# pc_healthypi_move_nRF5340_v5.net
KiCad netlist of a schematic drawn in EAGLE
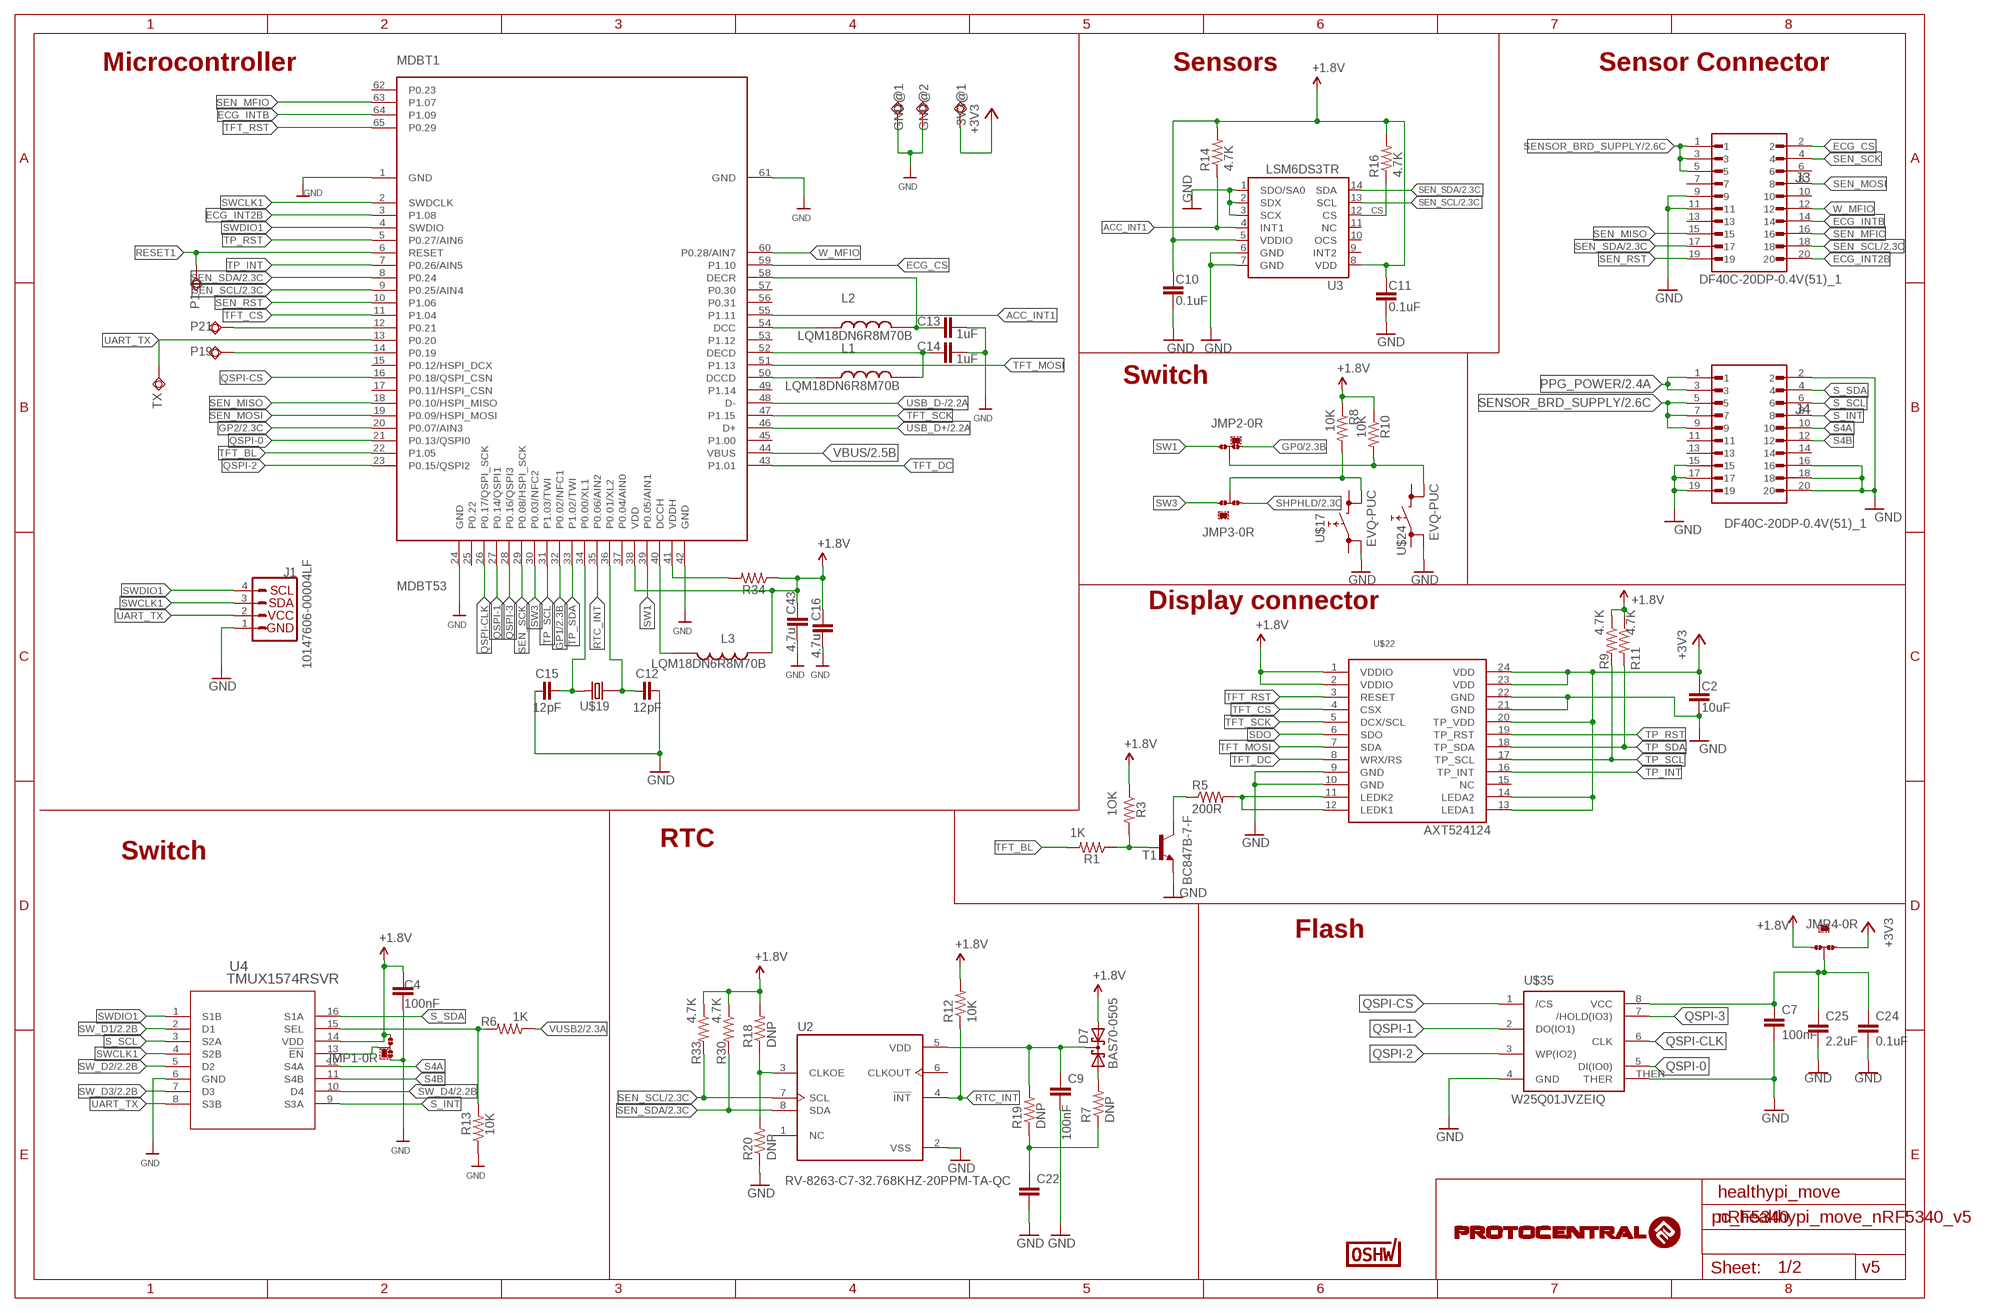
[diagram p0: schematic, sheet 1]
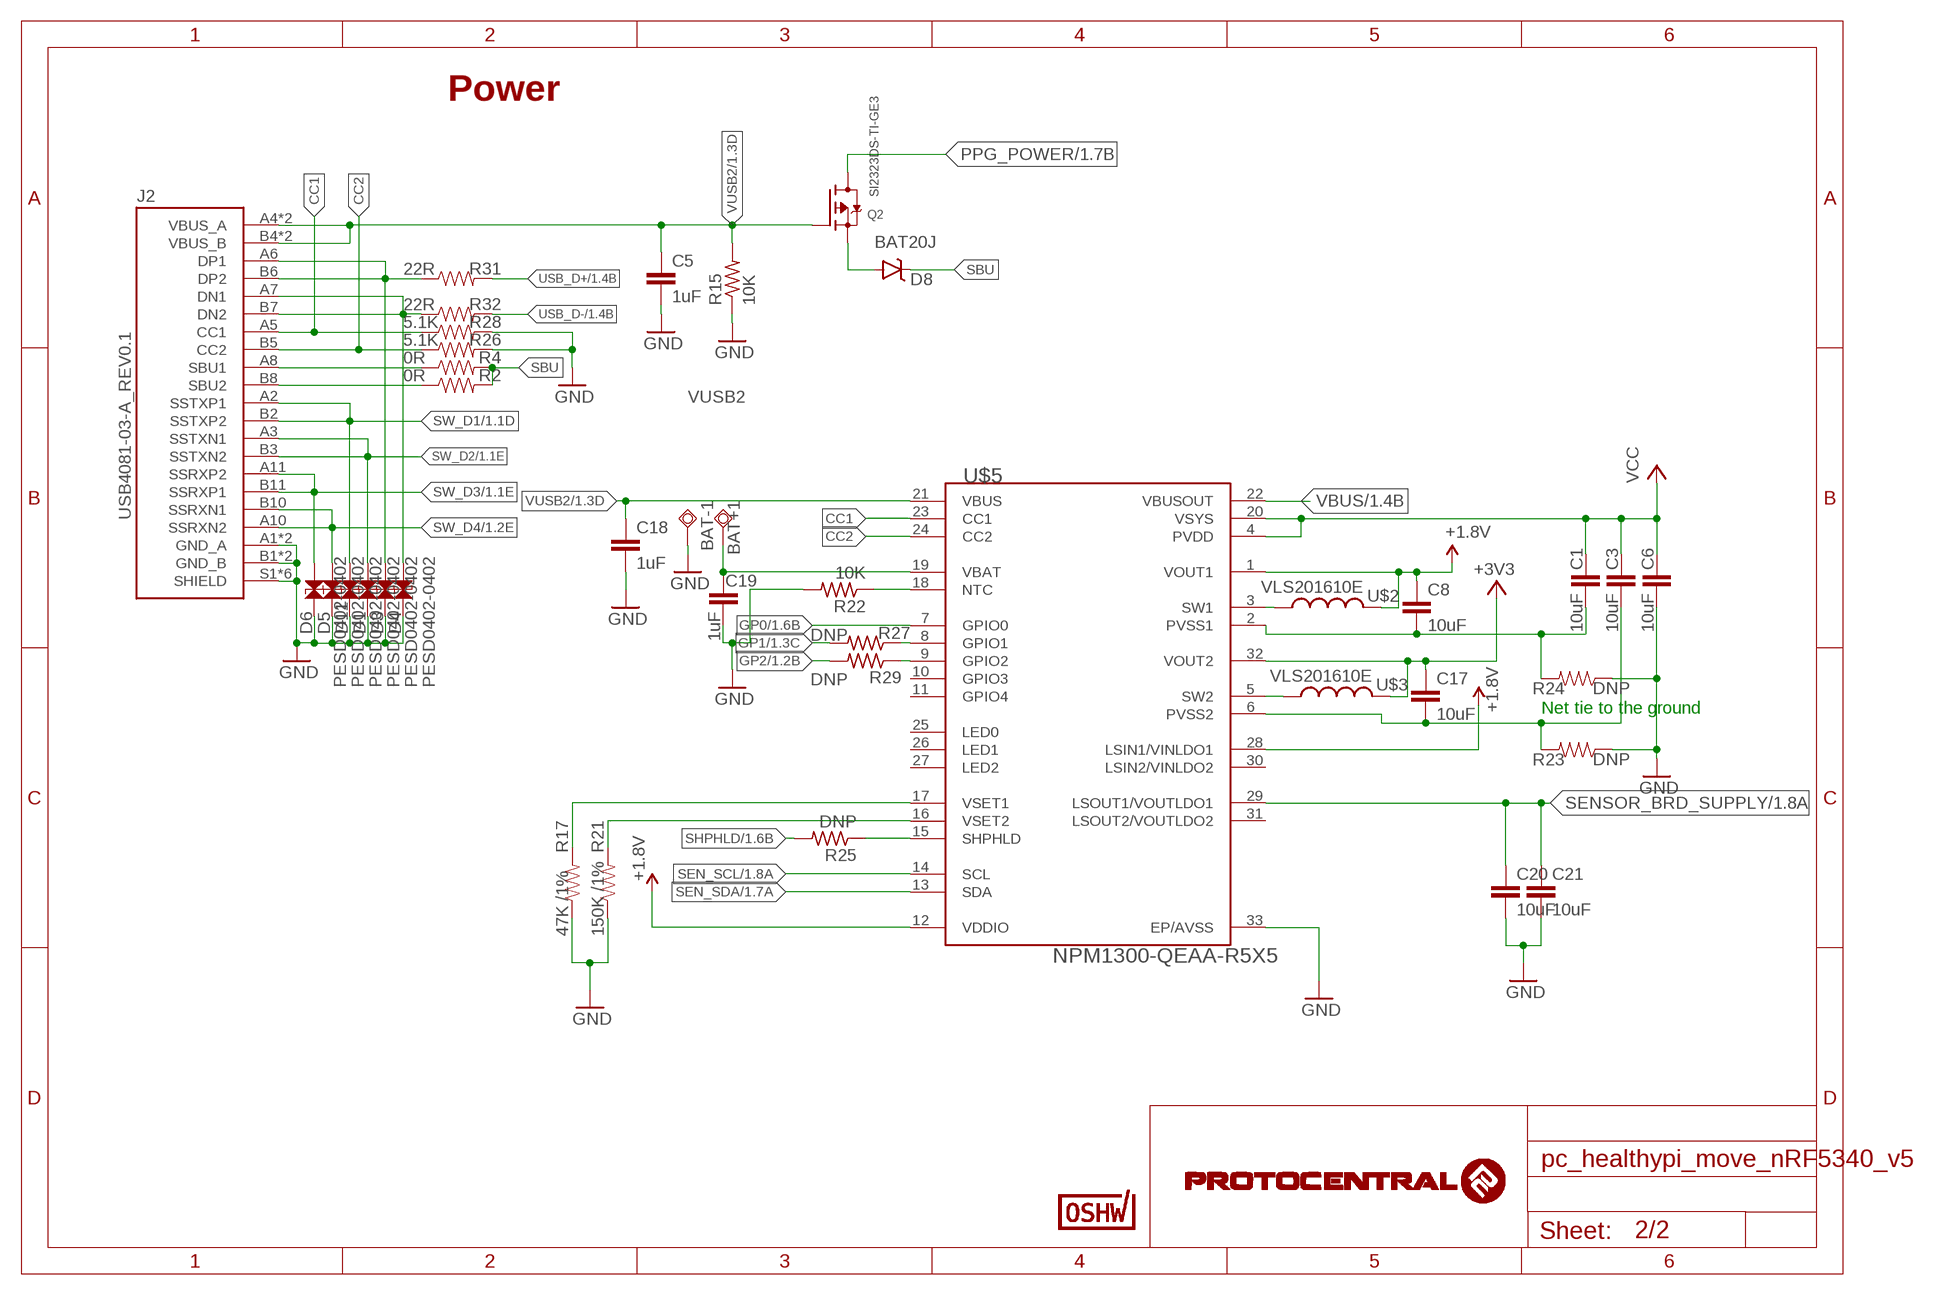
[diagram p1: schematic, sheet 2]

(export (version "E")
  (design (tool "Eeschema 10.0.6"))
  (components
    (comp (ref "BAT+1")
      (value "TPSQTP13SQ")
      (footprint "eagle-import:TP13SQ")
      (libsource (lib "eagle-import") (part "TPSQTP13SQ"))
    )
    (comp (ref "BAT-1")
      (value "TPSQTP13SQ")
      (footprint "eagle-import:TP13SQ")
      (libsource (lib "eagle-import") (part "TPSQTP13SQ"))
    )
    (comp (ref "C1")
      (value "10uF")
      (footprint "eagle-import:0402-TIGHT")
      (libsource (lib "eagle-import") (part "2.2UF-0402_TIGHT-10V-10%-X5R"))
    )
    (comp (ref "C3")
      (value "10uF")
      (footprint "eagle-import:0402-TIGHT")
      (libsource (lib "eagle-import") (part "2.2UF-0402_TIGHT-10V-10%-X5R"))
    )
    (comp (ref "C5")
      (value "1uF")
      (footprint "eagle-import:0402-TIGHT")
      (libsource (lib "eagle-import") (part "2.2UF-0402_TIGHT-10V-10%-X5R"))
    )
    (comp (ref "C6")
      (value "10uF")
      (footprint "eagle-import:0402-TIGHT")
      (libsource (lib "eagle-import") (part "2.2UF-0402_TIGHT-10V-10%-X5R"))
    )
    (comp (ref "C8")
      (value "10uF")
      (footprint "eagle-import:0402-TIGHT")
      (libsource (lib "eagle-import") (part "2.2UF-0402_TIGHT-10V-10%-X5R"))
    )
    (comp (ref "C17")
      (value "10uF")
      (footprint "eagle-import:0402-TIGHT")
      (libsource (lib "eagle-import") (part "2.2UF-0402_TIGHT-10V-10%-X5R"))
    )
    (comp (ref "C18")
      (value "1uF")
      (footprint "eagle-import:0402-TIGHT")
      (libsource (lib "eagle-import") (part "2.2UF-0402_TIGHT-10V-10%-X5R"))
    )
    (comp (ref "C19")
      (value "1uF")
      (footprint "eagle-import:0402-TIGHT")
      (libsource (lib "eagle-import") (part "2.2UF-0402_TIGHT-10V-10%-X5R"))
    )
    (comp (ref "C20")
      (value "10uF")
      (footprint "eagle-import:0402-TIGHT")
      (libsource (lib "eagle-import") (part "2.2UF-0402_TIGHT-10V-10%-X5R"))
    )
    (comp (ref "C21")
      (value "10uF")
      (footprint "eagle-import:0402-TIGHT")
      (libsource (lib "eagle-import") (part "2.2UF-0402_TIGHT-10V-10%-X5R"))
    )
    (comp (ref "D1")
      (value "PESD0402-0402")
      (footprint "eagle-import:0402")
      (fields
        (field (name "DIGIKEY_PART") "PESD0402-140CT-ND")
        (field (name "MOUSE_PART") "650-PESD0402-140")
      )
      (libsource (lib "eagle-import") (part "PESD0402-0402"))
    )
    (comp (ref "D3")
      (value "PESD0402-0402")
      (footprint "eagle-import:0402")
      (fields
        (field (name "DIGIKEY_PART") "PESD0402-140CT-ND")
        (field (name "MOUSE_PART") "650-PESD0402-140")
      )
      (libsource (lib "eagle-import") (part "PESD0402-0402"))
    )
    (comp (ref "D4")
      (value "PESD0402-0402")
      (footprint "eagle-import:0402")
      (fields
        (field (name "DIGIKEY_PART") "PESD0402-140CT-ND")
        (field (name "MOUSE_PART") "650-PESD0402-140")
      )
      (libsource (lib "eagle-import") (part "PESD0402-0402"))
    )
    (comp (ref "D5")
      (value "PESD0402-0402")
      (footprint "eagle-import:0402")
      (fields
        (field (name "DIGIKEY_PART") "PESD0402-140CT-ND")
        (field (name "MOUSE_PART") "650-PESD0402-140")
      )
      (libsource (lib "eagle-import") (part "PESD0402-0402"))
    )
    (comp (ref "D6")
      (value "PESD0402-0402")
      (footprint "eagle-import:0402")
      (fields
        (field (name "DIGIKEY_PART") "PESD0402-140CT-ND")
        (field (name "MOUSE_PART") "650-PESD0402-140")
      )
      (libsource (lib "eagle-import") (part "PESD0402-0402"))
    )
    (comp (ref "D8")
      (value "BAT20J")
      (footprint "eagle-import:SOD-323")
      (libsource (lib "eagle-import") (part "DIODE-SCHOTTKY-BAT20J"))
    )
    (comp (ref "D11")
      (value "PESD0402-0402")
      (footprint "eagle-import:0402")
      (fields
        (field (name "DIGIKEY_PART") "PESD0402-140CT-ND")
        (field (name "MOUSE_PART") "650-PESD0402-140")
      )
      (libsource (lib "eagle-import") (part "PESD0402-0402"))
    )
    (comp (ref "J2")
      (value "USB4081-03-A_REV0.1")
      (footprint "eagle-import:GCT_USB4081-03-A_REV0.1")
      (fields (field (name "MF") "Global Connector Technology") (field (name "MP") "USB4081-03-A"))
      (libsource (lib "eagle-import") (part "USB4081-03-A_REV0.1"))
    )
    (comp (ref "Q2")
      (value "SI2323DS-TI-GE3")
      (footprint "eagle-import:SOT23-R")
      (libsource (lib "eagle-import") (part "MOSFET-P"))
    )
    (comp (ref "R2")
      (value "0R")
      (footprint "eagle-import:0402-RES")
      (libsource (lib "eagle-import") (part "RESISTOR0402-RES"))
    )
    (comp (ref "R4")
      (value "0R")
      (footprint "eagle-import:0402-RES")
      (libsource (lib "eagle-import") (part "RESISTOR0402-RES"))
    )
    (comp (ref "R15")
      (value "10K")
      (footprint "eagle-import:R0402")
      (libsource (lib "eagle-import") (part "R-US_R0402"))
    )
    (comp (ref "R17")
      (value "47K /1%")
      (footprint "eagle-import:0402-RES")
      (libsource (lib "eagle-import") (part "RESISTOR0402-RES"))
    )
    (comp (ref "R21")
      (value "150K /1%")
      (footprint "eagle-import:0402-RES")
      (libsource (lib "eagle-import") (part "RESISTOR0402-RES"))
    )
    (comp (ref "R22")
      (value "10K")
      (footprint "eagle-import:R0402")
      (libsource (lib "eagle-import") (part "R-US_R0402"))
    )
    (comp (ref "R23")
      (value "DNP")
      (footprint "eagle-import:0402-RES")
      (libsource (lib "eagle-import") (part "RESISTOR0402-RES"))
    )
    (comp (ref "R24")
      (value "DNP")
      (footprint "eagle-import:0402-RES")
      (libsource (lib "eagle-import") (part "RESISTOR0402-RES"))
    )
    (comp (ref "R25")
      (value "DNP")
      (footprint "eagle-import:R0402")
      (libsource (lib "eagle-import") (part "R-US_R0402"))
    )
    (comp (ref "R26")
      (value "5.1K")
      (footprint "eagle-import:0402-RES")
      (libsource (lib "eagle-import") (part "RESISTOR0402-RES"))
    )
    (comp (ref "R27")
      (value "DNP")
      (footprint "eagle-import:R0402")
      (libsource (lib "eagle-import") (part "R-US_R0402"))
    )
    (comp (ref "R28")
      (value "5.1K")
      (footprint "eagle-import:0402-RES")
      (libsource (lib "eagle-import") (part "RESISTOR0402-RES"))
    )
    (comp (ref "R29")
      (value "DNP")
      (footprint "eagle-import:R0402")
      (libsource (lib "eagle-import") (part "R-US_R0402"))
    )
    (comp (ref "R31")
      (value "22R")
      (footprint "eagle-import:0402-RES")
      (libsource (lib "eagle-import") (part "RESISTOR0402-RES"))
    )
    (comp (ref "R32")
      (value "22R")
      (footprint "eagle-import:0402-RES")
      (libsource (lib "eagle-import") (part "RESISTOR0402-RES"))
    )
    (comp (ref "U$2")
      (value "VLS201610E")
      (footprint "eagle-import:VLS201610E")
      (libsource (lib "eagle-import") (part "VLS201610E"))
    )
    (comp (ref "U$3")
      (value "VLS201610E")
      (footprint "eagle-import:VLS201610E")
      (libsource (lib "eagle-import") (part "VLS201610E"))
    )
    (comp (ref "U$5")
      (value "NPM1300-QEAA-R5X5")
      (footprint "eagle-import:QFN32_5X5MC_MCH")
      (libsource (lib "eagle-import") (part "NPM1300-QEAA-R5X5"))
    )
    (comp (ref "U$40")
      (value "CERT-SMALL")
      (footprint "eagle-import:CERT-SMALL-SILK")
      (libsource (lib "eagle-import") (part "CERT-SMALL"))
    )
    (comp (ref "3V3@1")
      (value "TPSQTP13SQ")
      (footprint "eagle-import:TP13SQ")
      (libsource (lib "eagle-import") (part "TPSQTP13SQ"))
    )
    (comp (ref "C2")
      (value "10uF")
      (footprint "eagle-import:0603@1")
      (libsource (lib "eagle-import") (part "0.1UF-0603-100V-10%"))
    )
    (comp (ref "C4")
      (value "100nF")
      (footprint "eagle-import:0402-TIGHT")
      (libsource (lib "eagle-import") (part "2.2UF-0402_TIGHT-10V-10%-X5R"))
    )
    (comp (ref "C7")
      (value "100nF")
      (footprint "eagle-import:C0402")
      (libsource (lib "eagle-import") (part "C-EUC0402"))
    )
    (comp (ref "C9")
      (value "100nF")
      (footprint "eagle-import:C0402")
      (libsource (lib "eagle-import") (part "C-EUC0402"))
    )
    (comp (ref "C10")
      (value "0.1uF")
      (footprint "eagle-import:0402-TIGHT")
      (libsource (lib "eagle-import") (part "0.1UF-0402T-6.3V-10%-X7R"))
    )
    (comp (ref "C11")
      (value "0.1uF")
      (footprint "eagle-import:0402-TIGHT")
      (libsource (lib "eagle-import") (part "0.1UF-0402T-6.3V-10%-X7R"))
    )
    (comp (ref "C12")
      (value "12pF")
      (footprint "eagle-import:C0402")
      (libsource (lib "eagle-import") (part "CAPACITORS-0402"))
    )
    (comp (ref "C13")
      (value "1uF")
      (footprint "eagle-import:0402-TIGHT")
      (libsource (lib "eagle-import") (part "2.2UF-0402_TIGHT-10V-10%-X5R"))
    )
    (comp (ref "C14")
      (value "1uF")
      (footprint "eagle-import:0402-TIGHT")
      (libsource (lib "eagle-import") (part "2.2UF-0402_TIGHT-10V-10%-X5R"))
    )
    (comp (ref "C15")
      (value "12pF")
      (footprint "eagle-import:C0402")
      (libsource (lib "eagle-import") (part "CAPACITORS-0402"))
    )
    (comp (ref "C16")
      (value "4.7u")
      (footprint "eagle-import:C0402")
      (libsource (lib "eagle-import") (part "C-EUC0402"))
    )
    (comp (ref "C22")
      (value "C-EUC1210")
      (footprint "eagle-import:C1210")
      (libsource (lib "eagle-import") (part "C-EUC1210"))
    )
    (comp (ref "C24")
      (value "0.1uF")
      (footprint "eagle-import:0402-TIGHT")
      (libsource (lib "eagle-import") (part "0.1UF-0402T-6.3V-10%-X7R"))
    )
    (comp (ref "C25")
      (value "2.2uF")
      (footprint "eagle-import:0402-TIGHT")
      (libsource (lib "eagle-import") (part "2.2UF-0402_TIGHT-10V-10%-X5R"))
    )
    (comp (ref "C43")
      (value "4.7u")
      (footprint "eagle-import:C0402")
      (libsource (lib "eagle-import") (part "C-EUC0402"))
    )
    (comp (ref "D7")
      (value "BAS70-0505")
      (footprint "eagle-import:SOT23")
      (fields (field (name "MF") "Diotec") (field (name "MP") "BAS70-05"))
      (libsource (lib "eagle-import") (part "BAS70-0505"))
    )
    (comp (ref "GND@1")
      (value "TPSQTP13SQ")
      (footprint "eagle-import:TP13SQ")
      (libsource (lib "eagle-import") (part "TPSQTP13SQ"))
    )
    (comp (ref "GND@2")
      (value "TPSQTP13SQ")
      (footprint "eagle-import:TP13SQ")
      (libsource (lib "eagle-import") (part "TPSQTP13SQ"))
    )
    (comp (ref "J1")
      (value "10147606-00004LF")
      (footprint "eagle-import:JST04_1MM_RA")
      (libsource (lib "eagle-import") (part "QWIIC_CONNECTORJS-1MM"))
    )
    (comp (ref "J3")
      (value "DF40C-20DP-0.4V(51)_1")
      (footprint "eagle-import:HRS_DF40C-20DP-0.4V(51)")
      (fields (field (name "MANUFACTURER") "Hirose Electric"))
      (libsource (lib "eagle-import") (part "DF40C-20DP-0.4V(51)_1"))
    )
    (comp (ref "J4")
      (value "DF40C-20DP-0.4V(51)_1")
      (footprint "eagle-import:HRS_DF40C-20DP-0.4V(51)")
      (fields (field (name "MANUFACTURER") "Hirose Electric"))
      (libsource (lib "eagle-import") (part "DF40C-20DP-0.4V(51)_1"))
    )
    (comp (ref "JMP1")
      (value "0R-JUMPB")
      (footprint "eagle-import:B0R-JMP")
      (libsource (lib "eagle-import") (part "0R-JUMPB"))
    )
    (comp (ref "JMP2")
      (value "0R-JUMPB")
      (footprint "eagle-import:B0R-JMP")
      (libsource (lib "eagle-import") (part "0R-JUMPB"))
    )
    (comp (ref "JMP3")
      (value "0R-JUMPB")
      (footprint "eagle-import:B0R-JMP")
      (libsource (lib "eagle-import") (part "0R-JUMPB"))
    )
    (comp (ref "JMP4")
      (value "0R-JUMPB")
      (footprint "eagle-import:B0R-JMP")
      (libsource (lib "eagle-import") (part "0R-JUMPB"))
    )
    (comp (ref "L1")
      (value "LQM18DN6R8M70B")
      (footprint "eagle-import:INDC1608X95N")
      (fields (field (name "MF") "Murata"))
      (libsource (lib "eagle-import") (part "LQM18DN6R8M70B"))
    )
    (comp (ref "L2")
      (value "LQM18DN6R8M70B")
      (footprint "eagle-import:INDC1608X95N")
      (fields (field (name "MF") "Murata"))
      (libsource (lib "eagle-import") (part "LQM18DN6R8M70B"))
    )
    (comp (ref "L3")
      (value "LQM18DN6R8M70B")
      (footprint "eagle-import:INDC1608X95N")
      (fields (field (name "MF") "Murata"))
      (libsource (lib "eagle-import") (part "LQM18DN6R8M70B"))
    )
    (comp (ref "MDBT1")
      (value "MDBT53")
      (footprint "eagle-import:MDBT53")
      (libsource (lib "eagle-import") (part "MDBT53"))
    )
    (comp (ref "P1")
      (value "TPSQTP13SQ")
      (footprint "eagle-import:TP13SQ")
      (libsource (lib "eagle-import") (part "TPSQTP13SQ"))
    )
    (comp (ref "P19")
      (value "TPSQTP13SQ")
      (footprint "eagle-import:TP13SQ")
      (libsource (lib "eagle-import") (part "TPSQTP13SQ"))
    )
    (comp (ref "P21")
      (value "TPSQTP13SQ")
      (footprint "eagle-import:TP13SQ")
      (libsource (lib "eagle-import") (part "TPSQTP13SQ"))
    )
    (comp (ref "R1")
      (value "200")
      (footprint "eagle-import:R0402")
      (libsource (lib "eagle-import") (part "R-US_R0402"))
    )
    (comp (ref "R3")
      (value "200")
      (footprint "eagle-import:R0402")
      (libsource (lib "eagle-import") (part "R-US_R0402"))
    )
    (comp (ref "R5")
      (value "200R")
      (footprint "eagle-import:R0402")
      (libsource (lib "eagle-import") (part "R-US_R0402"))
    )
    (comp (ref "R6")
      (value "1K")
      (footprint "eagle-import:0402-RES")
      (libsource (lib "eagle-import") (part "RESISTOR0402-RES"))
    )
    (comp (ref "R7")
      (value "DNP")
      (footprint "eagle-import:R0402")
      (libsource (lib "eagle-import") (part "R-US_R0402"))
    )
    (comp (ref "R8")
      (value "10K")
      (footprint "eagle-import:R0402")
      (libsource (lib "eagle-import") (part "R-US_R0402"))
    )
    (comp (ref "R9")
      (value "4.7K")
      (footprint "eagle-import:R0402")
      (libsource (lib "eagle-import") (part "R-US_R0402"))
    )
    (comp (ref "R10")
      (value "10K")
      (footprint "eagle-import:R0402")
      (libsource (lib "eagle-import") (part "R-US_R0402"))
    )
    (comp (ref "R11")
      (value "4.7K")
      (footprint "eagle-import:R0402")
      (libsource (lib "eagle-import") (part "R-US_R0402"))
    )
    (comp (ref "R12")
      (value "10K")
      (footprint "eagle-import:R0402")
      (libsource (lib "eagle-import") (part "R-US_R0402"))
    )
    (comp (ref "R13")
      (value "10K")
      (footprint "eagle-import:R0402")
      (libsource (lib "eagle-import") (part "R-US_R0402"))
    )
    (comp (ref "R14")
      (value "4.7K")
      (footprint "eagle-import:R0402")
      (libsource (lib "eagle-import") (part "R-US_R0402"))
    )
    (comp (ref "R16")
      (value "4.7K")
      (footprint "eagle-import:R0402")
      (libsource (lib "eagle-import") (part "R-US_R0402"))
    )
    (comp (ref "R18")
      (value "DNP")
      (footprint "eagle-import:R0402")
      (libsource (lib "eagle-import") (part "R-US_R0402"))
    )
    (comp (ref "R19")
      (value "DNP")
      (footprint "eagle-import:R0402")
      (libsource (lib "eagle-import") (part "R-US_R0402"))
    )
    (comp (ref "R20")
      (value "DNP")
      (footprint "eagle-import:R0402")
      (libsource (lib "eagle-import") (part "R-US_R0402"))
    )
    (comp (ref "R30")
      (value "4.7K")
      (footprint "eagle-import:R0402")
      (libsource (lib "eagle-import") (part "R-US_R0402"))
    )
    (comp (ref "R33")
      (value "4.7K")
      (footprint "eagle-import:R0402")
      (libsource (lib "eagle-import") (part "R-US_R0402"))
    )
    (comp (ref "R34")
      (value "200")
      (footprint "eagle-import:R0402")
      (libsource (lib "eagle-import") (part "R-US_R0402"))
    )
    (comp (ref "T1")
      (value "BC847B-7-F")
      (footprint "eagle-import:SOT23-BEC")
      (libsource (lib "eagle-import") (part "-NPN-SOT23-BECMMBT2222ALT1"))
    )
    (comp (ref "TX")
      (value "TPSQTP13SQ")
      (footprint "eagle-import:TP13SQ")
      (libsource (lib "eagle-import") (part "TPSQTP13SQ"))
    )
    (comp (ref "U$9")
      (value "CERT-SMALL")
      (footprint "eagle-import:CERT-SMALL-SILK")
      (libsource (lib "eagle-import") (part "CERT-SMALL"))
    )
    (comp (ref "U$17")
      (value "EVQ-PUC")
      (footprint "eagle-import:EVQ-PUC")
      (libsource (lib "eagle-import") (part "EVQ-PUC"))
    )
    (comp (ref "U$19")
      (value "520-327-12.5-34B(32.768KHZ)")
      (footprint "eagle-import:ECX-31B")
      (libsource (lib "eagle-import") (part "ECS-X-34B"))
    )
    (comp (ref "U$22")
      (value "AXT524124")
      (footprint "eagle-import:AXT524124")
      (libsource (lib "eagle-import") (part "AXT524124"))
    )
    (comp (ref "U$24")
      (value "EVQ-PUC")
      (footprint "eagle-import:EVQ-PUC")
      (libsource (lib "eagle-import") (part "EVQ-PUC"))
    )
    (comp (ref "U$35")
      (value "W25Q01JVZEIQ")
      (footprint "eagle-import:WSON-08")
      (libsource (lib "eagle-import") (part "W25N01GVZEIG"))
    )
    (comp (ref "U2")
      (value "RV-8263-C7-32.768KHZ-20PPM-TA-QC")
      (footprint "eagle-import:IC_RV-8263-C7-32.768KHZ-20PPM-TA-QC")
      (fields (field (name "MF") "Micro Crystal"))
      (libsource (lib "eagle-import") (part "RV-8263-C7-32.768KHZ-20PPM-TA-QC"))
    )
    (comp (ref "U3")
      (value "LSM6DS3TR")
      (footprint "eagle-import:LGA14L")
      (libsource (lib "eagle-import") (part "LSM6DS3"))
    )
    (comp (ref "U4")
      (value "TMUX1574RSVR")
      (footprint "eagle-import:RSV16_TEX")
      (fields (field (name "COPYRIGHT") "Copyright (C) 2024 Ultra Librarian. All rights reserved."))
      (libsource (lib "eagle-import") (part "TMUX1574RSVR"))
    )
  )
  (nets
    (net (code "1") (name "+1.8V") (class "Default")
      (node (ref "C10") (pin "1") (pinfunction "1_1") (pintype "passive"))
      (node (ref "C11") (pin "1") (pinfunction "1_1") (pintype "passive"))
      (node (ref "C16") (pin "1") (pinfunction "1_1") (pintype "passive"))
      (node (ref "C4") (pin "1") (pinfunction "1_1") (pintype "passive"))
      (node (ref "C43") (pin "1") (pinfunction "1_1") (pintype "passive"))
      (node (ref "C8") (pin "1") (pinfunction "1_1") (pintype "passive"))
      (node (ref "D7") (pin "2") (pinfunction "A2_2") (pintype "passive"))
      (node (ref "JMP1") (pin "3") (pinfunction "3_3") (pintype "passive"))
      (node (ref "JMP4") (pin "3") (pinfunction "3_3") (pintype "passive"))
      (node (ref "L3") (pin "1") (pinfunction "1_1") (pintype "passive"))
      (node (ref "MDBT1") (pin "38") (pinfunction "VDD_38") (pintype "bidirectional"))
      (node (ref "R10") (pin "1") (pinfunction "1_1") (pintype "passive"))
      (node (ref "R11") (pin "1") (pinfunction "1_1") (pintype "passive"))
      (node (ref "R12") (pin "2") (pinfunction "2_2") (pintype "passive"))
      (node (ref "R14") (pin "2") (pinfunction "2_2") (pintype "passive"))
      (node (ref "R16") (pin "2") (pinfunction "2_2") (pintype "passive"))
      (node (ref "R18") (pin "2") (pinfunction "2_2") (pintype "passive"))
      (node (ref "R3") (pin "1") (pinfunction "1_1") (pintype "passive"))
      (node (ref "R30") (pin "1") (pinfunction "1_1") (pintype "passive"))
      (node (ref "R33") (pin "1") (pinfunction "1_1") (pintype "passive"))
      (node (ref "R34") (pin "1") (pinfunction "1_1") (pintype "passive"))
      (node (ref "R8") (pin "1") (pinfunction "1_1") (pintype "passive"))
      (node (ref "R9") (pin "1") (pinfunction "1_1") (pintype "passive"))
      (node (ref "U$2") (pin "2") (pinfunction "2_2") (pintype "passive"))
      (node (ref "U$22") (pin "1") (pinfunction "VDDIO_1") (pintype "bidirectional"))
      (node (ref "U$22") (pin "2") (pinfunction "VDDIO_2") (pintype "bidirectional"))
      (node (ref "U$5") (pin "1") (pinfunction "VOUT1_1") (pintype "bidirectional"))
      (node (ref "U$5") (pin "12") (pinfunction "VDDIO_12") (pintype "bidirectional"))
      (node (ref "U$5") (pin "28") (pinfunction "LSIN1/VINLDO1_28") (pintype "bidirectional"))
      (node (ref "U3") (pin "5") (pinfunction "VDDIO_5") (pintype "bidirectional"))
      (node (ref "U3") (pin "8") (pinfunction "VDD_8") (pintype "bidirectional"))
      (node (ref "U4") (pin "14") (pinfunction "VDD_14") (pintype "power_in"))
    )
    (net (code "2") (name "+3V3") (class "Default")
      (node (ref "3V3@1") (pin "TP") (pinfunction "TP_TP") (pintype "input"))
      (node (ref "C17") (pin "1") (pinfunction "1_1") (pintype "passive"))
      (node (ref "C2") (pin "1") (pinfunction "1_1") (pintype "passive"))
      (node (ref "JMP4") (pin "1") (pinfunction "1_1") (pintype "passive"))
      (node (ref "U$22") (pin "13") (pinfunction "LEDA1_13") (pintype "bidirectional"))
      (node (ref "U$22") (pin "14") (pinfunction "LEDA2_14") (pintype "bidirectional"))
      (node (ref "U$22") (pin "20") (pinfunction "TP_VDD_20") (pintype "bidirectional"))
      (node (ref "U$22") (pin "23") (pinfunction "VDD_23") (pintype "bidirectional"))
      (node (ref "U$22") (pin "24") (pinfunction "VDD_24") (pintype "bidirectional"))
      (node (ref "U$3") (pin "2") (pinfunction "2_2") (pintype "passive"))
      (node (ref "U$5") (pin "32") (pinfunction "VOUT2_32") (pintype "bidirectional"))
    )
    (net (code "3") (name "ACC_INT1") (class "Default")
      (node (ref "MDBT1") (pin "55") (pinfunction "P1.11_55") (pintype "bidirectional"))
      (node (ref "R14") (pin "1") (pinfunction "1_1") (pintype "passive"))
      (node (ref "U3") (pin "4") (pinfunction "INT1_4") (pintype "bidirectional"))
    )
    (net (code "4") (name "CC1") (class "Default")
      (node (ref "J2") (pin "A5") (pinfunction "CC1_A5") (pintype "bidirectional"))
      (node (ref "R28") (pin "1") (pinfunction "1_1") (pintype "passive"))
      (node (ref "U$5") (pin "23") (pinfunction "CC1_23") (pintype "bidirectional"))
    )
    (net (code "5") (name "CC2") (class "Default")
      (node (ref "J2") (pin "B5") (pinfunction "CC2_B5") (pintype "bidirectional"))
      (node (ref "R26") (pin "1") (pinfunction "1_1") (pintype "passive"))
      (node (ref "U$5") (pin "24") (pinfunction "CC2_24") (pintype "bidirectional"))
    )
    (net (code "6") (name "CS") (class "Default")
      (node (ref "R16") (pin "1") (pinfunction "1_1") (pintype "passive"))
      (node (ref "U3") (pin "12") (pinfunction "CS_12") (pintype "bidirectional"))
    )
    (net (code "7") (name "ECG_CS") (class "Default")
      (node (ref "J3") (pin "2") (pinfunction "2_2") (pintype "passive"))
      (node (ref "MDBT1") (pin "59") (pinfunction "P1.10_59") (pintype "bidirectional"))
    )
    (net (code "8") (name "ECG_INT2B") (class "Default")
      (node (ref "J3") (pin "20") (pinfunction "20_20") (pintype "passive"))
      (node (ref "MDBT1") (pin "3") (pinfunction "P1.08_3") (pintype "bidirectional"))
    )
    (net (code "9") (name "ECG_INTB") (class "Default")
      (node (ref "J3") (pin "14") (pinfunction "14_14") (pintype "passive"))
      (node (ref "MDBT1") (pin "64") (pinfunction "P1.09_64") (pintype "bidirectional"))
    )
    (net (code "10") (name "GND") (class "Default")
      (node (ref "BAT-1") (pin "TP") (pinfunction "TP_TP") (pintype "input"))
      (node (ref "C10") (pin "2") (pinfunction "2_2") (pintype "passive"))
      (node (ref "C11") (pin "2") (pinfunction "2_2") (pintype "passive"))
      (node (ref "C12") (pin "2") (pinfunction "2_2") (pintype "passive"))
      (node (ref "C13") (pin "2") (pinfunction "2_2") (pintype "passive"))
      (node (ref "C14") (pin "2") (pinfunction "2_2") (pintype "passive"))
      (node (ref "C15") (pin "1") (pinfunction "1_1") (pintype "passive"))
      (node (ref "C16") (pin "2") (pinfunction "2_2") (pintype "passive"))
      (node (ref "C18") (pin "2") (pinfunction "2_2") (pintype "passive"))
      (node (ref "C19") (pin "2") (pinfunction "2_2") (pintype "passive"))
      (node (ref "C2") (pin "2") (pinfunction "2_2") (pintype "passive"))
      (node (ref "C20") (pin "2") (pinfunction "2_2") (pintype "passive"))
      (node (ref "C21") (pin "2") (pinfunction "2_2") (pintype "passive"))
      (node (ref "C22") (pin "2") (pinfunction "2_2") (pintype "passive"))
      (node (ref "C24") (pin "2") (pinfunction "2_2") (pintype "passive"))
      (node (ref "C25") (pin "2") (pinfunction "2_2") (pintype "passive"))
      (node (ref "C4") (pin "2") (pinfunction "2_2") (pintype "passive"))
      (node (ref "C43") (pin "2") (pinfunction "2_2") (pintype "passive"))
      (node (ref "C5") (pin "2") (pinfunction "2_2") (pintype "passive"))
      (node (ref "C6") (pin "2") (pinfunction "2_2") (pintype "passive"))
      (node (ref "C7") (pin "2") (pinfunction "2_2") (pintype "passive"))
      (node (ref "C9") (pin "2") (pinfunction "2_2") (pintype "passive"))
      (node (ref "D1") (pin "1") (pinfunction "1_1") (pintype "bidirectional"))
      (node (ref "D11") (pin "1") (pinfunction "1_1") (pintype "bidirectional"))
      (node (ref "D3") (pin "1") (pinfunction "1_1") (pintype "bidirectional"))
      (node (ref "D4") (pin "1") (pinfunction "1_1") (pintype "bidirectional"))
      (node (ref "D5") (pin "1") (pinfunction "1_1") (pintype "bidirectional"))
      (node (ref "D6") (pin "1") (pinfunction "1_1") (pintype "bidirectional"))
      (node (ref "GND@1") (pin "TP") (pinfunction "TP_TP") (pintype "input"))
      (node (ref "GND@2") (pin "TP") (pinfunction "TP_TP") (pintype "input"))
      (node (ref "J1") (pin "1") (pinfunction "1_1") (pintype "power_in"))
      (node (ref "J2") (pin "A1") (pinfunction "GND_A_A1") (pintype "power_in"))
      (node (ref "J2") (pin "A12") (pinfunction "GND_A_A12") (pintype "power_in"))
      (node (ref "J2") (pin "B1") (pinfunction "GND_B_B1") (pintype "power_in"))
      (node (ref "J2") (pin "B12") (pinfunction "GND_B_B12") (pintype "power_in"))
      (node (ref "J2") (pin "S1") (pinfunction "SHIELD_S1") (pintype "passive"))
      (node (ref "J2") (pin "S2") (pinfunction "SHIELD_S2") (pintype "passive"))
      (node (ref "J2") (pin "S3") (pinfunction "SHIELD_S3") (pintype "passive"))
      (node (ref "J2") (pin "S4") (pinfunction "SHIELD_S4") (pintype "passive"))
      (node (ref "J2") (pin "S5") (pinfunction "SHIELD_S5") (pintype "passive"))
      (node (ref "J2") (pin "S6") (pinfunction "SHIELD_S6") (pintype "passive"))
      (node (ref "J3") (pin "11") (pinfunction "11_11") (pintype "passive"))
      (node (ref "J3") (pin "9") (pinfunction "9_9") (pintype "passive"))
      (node (ref "J4") (pin "15") (pinfunction "15_15") (pintype "passive"))
      (node (ref "J4") (pin "16") (pinfunction "16_16") (pintype "passive"))
      (node (ref "J4") (pin "17") (pinfunction "17_17") (pintype "passive"))
      (node (ref "J4") (pin "18") (pinfunction "18_18") (pintype "passive"))
      (node (ref "J4") (pin "19") (pinfunction "19_19") (pintype "passive"))
      (node (ref "J4") (pin "2") (pinfunction "2_2") (pintype "passive"))
      (node (ref "J4") (pin "20") (pinfunction "20_20") (pintype "passive"))
      (node (ref "JMP1") (pin "1") (pinfunction "1_1") (pintype "passive"))
      (node (ref "MDBT1") (pin "1") (pinfunction "GND_1") (pintype "bidirectional"))
      (node (ref "MDBT1") (pin "24") (pinfunction "GND_24") (pintype "bidirectional"))
      (node (ref "MDBT1") (pin "42") (pinfunction "GND_42") (pintype "bidirectional"))
      (node (ref "MDBT1") (pin "61") (pinfunction "GND_61") (pintype "bidirectional"))
      (node (ref "R13") (pin "1") (pinfunction "1_1") (pintype "passive"))
      (node (ref "R15") (pin "1") (pinfunction "1_1") (pintype "passive"))
      (node (ref "R17") (pin "1") (pinfunction "1_1") (pintype "passive"))
      (node (ref "R20") (pin "1") (pinfunction "1_1") (pintype "passive"))
      (node (ref "R21") (pin "1") (pinfunction "1_1") (pintype "passive"))
      (node (ref "R22") (pin "2") (pinfunction "2_2") (pintype "passive"))
      (node (ref "R23") (pin "1") (pinfunction "1_1") (pintype "passive"))
      (node (ref "R24") (pin "1") (pinfunction "1_1") (pintype "passive"))
      (node (ref "R26") (pin "2") (pinfunction "2_2") (pintype "passive"))
      (node (ref "R28") (pin "2") (pinfunction "2_2") (pintype "passive"))
      (node (ref "T1") (pin "E") (pinfunction "E_E") (pintype "passive"))
      (node (ref "U$17") (pin "3") (pinfunction "0_3") (pintype "passive"))
      (node (ref "U$22") (pin "10") (pinfunction "GND_10") (pintype "bidirectional"))
      (node (ref "U$22") (pin "21") (pinfunction "GND_21") (pintype "bidirectional"))
      (node (ref "U$22") (pin "22") (pinfunction "GND_22") (pintype "bidirectional"))
      (node (ref "U$22") (pin "9") (pinfunction "GND_9") (pintype "bidirectional"))
      (node (ref "U$24") (pin "3") (pinfunction "0_3") (pintype "passive"))
      (node (ref "U$35") (pin "4") (pinfunction "GND_4") (pintype "bidirectional"))
      (node (ref "U$35") (pin "THER") (pinfunction "THER_THER") (pintype "bidirectional"))
      (node (ref "U$5") (pin "33") (pinfunction "EP/AVSS_33") (pintype "bidirectional"))
      (node (ref "U2") (pin "2") (pinfunction "VSS_2") (pintype "power_in"))
      (node (ref "U3") (pin "1") (pinfunction "SDO/SA0_1") (pintype "bidirectional"))
      (node (ref "U3") (pin "2") (pinfunction "SDX_2") (pintype "bidirectional"))
      (node (ref "U3") (pin "3") (pinfunction "SCX_3") (pintype "bidirectional"))
      (node (ref "U3") (pin "6") (pinfunction "GND_6") (pintype "bidirectional"))
      (node (ref "U3") (pin "7") (pinfunction "GND_7") (pintype "bidirectional"))
      (node (ref "U4") (pin "6") (pinfunction "GND_6") (pintype "passive"))
    )
    (net (code "11") (name "GP0") (class "Default")
      (node (ref "JMP2") (pin "1") (pinfunction "1_1") (pintype "passive"))
      (node (ref "U$5") (pin "7") (pinfunction "GPIO0_7") (pintype "bidirectional"))
    )
    (net (code "12") (name "GP1") (class "Default")
      (node (ref "MDBT1") (pin "32") (pinfunction "P0.02/NFC1_32") (pintype "bidirectional"))
      (node (ref "R27") (pin "2") (pinfunction "2_2") (pintype "passive"))
    )
    (net (code "13") (name "GP2") (class "Default")
      (node (ref "MDBT1") (pin "20") (pinfunction "P0.07/AIN3_20") (pintype "bidirectional"))
      (node (ref "R29") (pin "2") (pinfunction "2_2") (pintype "passive"))
    )
    (net (code "14") (name "Net-(C22-Pad1)") (class "Default")
      (node (ref "C22") (pin "1") (pinfunction "1_1") (pintype "passive"))
      (node (ref "R19") (pin "1") (pinfunction "1_1") (pintype "passive"))
      (node (ref "R7") (pin "1") (pinfunction "1_1") (pintype "passive"))
    )
    (net (code "15") (name "Net-(D7-A1)") (class "Default")
      (node (ref "D7") (pin "1") (pinfunction "A1_1") (pintype "passive"))
      (node (ref "R7") (pin "2") (pinfunction "2_2") (pintype "passive"))
    )
    (net (code "16") (name "Net-(D7-K1K2)") (class "Default")
      (node (ref "C9") (pin "1") (pinfunction "1_1") (pintype "passive"))
      (node (ref "D7") (pin "3") (pinfunction "K1K2_3") (pintype "passive"))
      (node (ref "R19") (pin "2") (pinfunction "2_2") (pintype "passive"))
      (node (ref "U2") (pin "5") (pinfunction "VDD_5") (pintype "power_in"))
    )
    (net (code "17") (name "Net-(J2-DN1)") (class "Default")
      (node (ref "D4") (pin "2") (pinfunction "2_2") (pintype "bidirectional"))
      (node (ref "J2") (pin "A7") (pinfunction "DN1_A7") (pintype "bidirectional"))
      (node (ref "J2") (pin "B7") (pinfunction "DN2_B7") (pintype "bidirectional"))
      (node (ref "R32") (pin "1") (pinfunction "1_1") (pintype "passive"))
    )
    (net (code "18") (name "Net-(J2-DP1)") (class "Default")
      (node (ref "D3") (pin "2") (pinfunction "2_2") (pintype "bidirectional"))
      (node (ref "J2") (pin "A6") (pinfunction "DP1_A6") (pintype "bidirectional"))
      (node (ref "J2") (pin "B6") (pinfunction "DP2_B6") (pintype "bidirectional"))
      (node (ref "R31") (pin "1") (pinfunction "1_1") (pintype "passive"))
    )
    (net (code "19") (name "Net-(J2-SBU1)") (class "Default")
      (node (ref "J2") (pin "A8") (pinfunction "SBU1_A8") (pintype "bidirectional"))
      (node (ref "R4") (pin "1") (pinfunction "1_1") (pintype "passive"))
    )
    (net (code "20") (name "Net-(J2-SBU2)") (class "Default")
      (node (ref "J2") (pin "B8") (pinfunction "SBU2_B8") (pintype "bidirectional"))
      (node (ref "R2") (pin "1") (pinfunction "1_1") (pintype "passive"))
    )
    (net (code "21") (name "Net-(JMP2-Pad2)") (class "Default")
      (node (ref "JMP2") (pin "2") (pinfunction "2_2") (pintype "passive"))
      (node (ref "R10") (pin "2") (pinfunction "2_2") (pintype "passive"))
      (node (ref "U$24") (pin "2") (pinfunction "1_2") (pintype "passive"))
    )
    (net (code "22") (name "Net-(JMP3-Pad2)") (class "Default")
      (node (ref "JMP3") (pin "2") (pinfunction "2_2") (pintype "passive"))
      (node (ref "R8") (pin "2") (pinfunction "2_2") (pintype "passive"))
      (node (ref "U$17") (pin "2") (pinfunction "1_2") (pintype "passive"))
    )
    (net (code "23") (name "Net-(MDBT1-DCC)") (class "Default")
      (node (ref "L2") (pin "1") (pinfunction "1_1") (pintype "passive"))
      (node (ref "MDBT1") (pin "54") (pinfunction "DCC_54") (pintype "bidirectional"))
    )
    (net (code "24") (name "Net-(MDBT1-DCCD)") (class "Default")
      (node (ref "L1") (pin "1") (pinfunction "1_1") (pintype "passive"))
      (node (ref "MDBT1") (pin "50") (pinfunction "DCCD_50") (pintype "bidirectional"))
    )
    (net (code "25") (name "Net-(MDBT1-DCCH)") (class "Default")
      (node (ref "L3") (pin "2") (pinfunction "2_2") (pintype "passive"))
      (node (ref "MDBT1") (pin "40") (pinfunction "DCCH_40") (pintype "bidirectional"))
    )
    (net (code "26") (name "Net-(MDBT1-DECD)") (class "Default")
      (node (ref "C14") (pin "1") (pinfunction "1_1") (pintype "passive"))
      (node (ref "L1") (pin "2") (pinfunction "2_2") (pintype "passive"))
      (node (ref "MDBT1") (pin "52") (pinfunction "DECD_52") (pintype "bidirectional"))
    )
    (net (code "27") (name "Net-(MDBT1-DECR)") (class "Default")
      (node (ref "C13") (pin "1") (pinfunction "1_1") (pintype "passive"))
      (node (ref "L2") (pin "2") (pinfunction "2_2") (pintype "passive"))
      (node (ref "MDBT1") (pin "58") (pinfunction "DECR_58") (pintype "bidirectional"))
    )
    (net (code "28") (name "Net-(MDBT1-P0.00{slash}XL1)") (class "Default")
      (node (ref "C15") (pin "2") (pinfunction "2_2") (pintype "passive"))
      (node (ref "MDBT1") (pin "34") (pinfunction "P0.00/XL1_34") (pintype "bidirectional"))
      (node (ref "U$19") (pin "P$2") (pinfunction "2_P$2") (pintype "passive"))
    )
    (net (code "29") (name "Net-(MDBT1-P0.01{slash}XL2)") (class "Default")
      (node (ref "C12") (pin "1") (pinfunction "1_1") (pintype "passive"))
      (node (ref "MDBT1") (pin "36") (pinfunction "P0.01/XL2_36") (pintype "bidirectional"))
      (node (ref "U$19") (pin "P$1") (pinfunction "1_P$1") (pintype "passive"))
    )
    (net (code "30") (name "Net-(MDBT1-P0.19)") (class "Default")
      (node (ref "MDBT1") (pin "14") (pinfunction "P0.19_14") (pintype "bidirectional"))
      (node (ref "P19") (pin "TP") (pinfunction "TP_TP") (pintype "input"))
    )
    (net (code "31") (name "Net-(MDBT1-P0.21)") (class "Default")
      (node (ref "MDBT1") (pin "12") (pinfunction "P0.21_12") (pintype "bidirectional"))
      (node (ref "P21") (pin "TP") (pinfunction "TP_TP") (pintype "input"))
    )
    (net (code "32") (name "Net-(MDBT1-VDDH)") (class "Default")
      (node (ref "MDBT1") (pin "41") (pinfunction "VDDH_41") (pintype "bidirectional"))
      (node (ref "R34") (pin "2") (pinfunction "2_2") (pintype "passive"))
    )
    (net (code "33") (name "Net-(Q2-S)") (class "Default")
      (node (ref "D8") (pin "A") (pinfunction "A_A") (pintype "passive"))
      (node (ref "Q2") (pin "2") (pinfunction "S_2") (pintype "passive"))
    )
    (net (code "34") (name "Net-(R1-Pad1)") (class "Default")
      (node (ref "R1") (pin "1") (pinfunction "1_1") (pintype "passive"))
      (node (ref "R3") (pin "2") (pinfunction "2_2") (pintype "passive"))
      (node (ref "T1") (pin "B") (pinfunction "B_B") (pintype "passive"))
    )
    (net (code "35") (name "Net-(R5-Pad1)") (class "Default")
      (node (ref "R5") (pin "1") (pinfunction "1_1") (pintype "passive"))
      (node (ref "T1") (pin "C") (pinfunction "C_C") (pintype "passive"))
    )
    (net (code "36") (name "Net-(U$5-GPIO1)") (class "Default")
      (node (ref "R27") (pin "1") (pinfunction "1_1") (pintype "passive"))
      (node (ref "U$5") (pin "8") (pinfunction "GPIO1_8") (pintype "bidirectional"))
    )
    (net (code "37") (name "Net-(U$5-GPIO2)") (class "Default")
      (node (ref "R29") (pin "1") (pinfunction "1_1") (pintype "passive"))
      (node (ref "U$5") (pin "9") (pinfunction "GPIO2_9") (pintype "bidirectional"))
    )
    (net (code "38") (name "Net-(U$5-NTC)") (class "Default")
      (node (ref "R22") (pin "1") (pinfunction "1_1") (pintype "passive"))
      (node (ref "U$5") (pin "18") (pinfunction "NTC_18") (pintype "bidirectional"))
    )
    (net (code "39") (name "Net-(U$5-PVSS1)") (class "Default")
      (node (ref "C1") (pin "2") (pinfunction "2_2") (pintype "passive"))
      (node (ref "C8") (pin "2") (pinfunction "2_2") (pintype "passive"))
      (node (ref "R24") (pin "2") (pinfunction "2_2") (pintype "passive"))
      (node (ref "U$5") (pin "2") (pinfunction "PVSS1_2") (pintype "bidirectional"))
    )
    (net (code "40") (name "Net-(U$5-PVSS2)") (class "Default")
      (node (ref "C17") (pin "2") (pinfunction "2_2") (pintype "passive"))
      (node (ref "C3") (pin "2") (pinfunction "2_2") (pintype "passive"))
      (node (ref "R23") (pin "2") (pinfunction "2_2") (pintype "passive"))
      (node (ref "U$5") (pin "6") (pinfunction "PVSS2_6") (pintype "bidirectional"))
    )
    (net (code "41") (name "Net-(U$5-SHPHLD)") (class "Default")
      (node (ref "R25") (pin "1") (pinfunction "1_1") (pintype "passive"))
      (node (ref "U$5") (pin "15") (pinfunction "SHPHLD_15") (pintype "bidirectional"))
    )
    (net (code "42") (name "Net-(U$5-SW1)") (class "Default")
      (node (ref "U$2") (pin "1") (pinfunction "1_1") (pintype "passive"))
      (node (ref "U$5") (pin "3") (pinfunction "SW1_3") (pintype "bidirectional"))
    )
    (net (code "43") (name "Net-(U$5-SW2)") (class "Default")
      (node (ref "U$3") (pin "1") (pinfunction "1_1") (pintype "passive"))
      (node (ref "U$5") (pin "5") (pinfunction "SW2_5") (pintype "bidirectional"))
    )
    (net (code "44") (name "Net-(U$5-VBAT)") (class "Default")
      (node (ref "BAT+1") (pin "TP") (pinfunction "TP_TP") (pintype "input"))
      (node (ref "C19") (pin "1") (pinfunction "1_1") (pintype "passive"))
      (node (ref "U$5") (pin "19") (pinfunction "VBAT_19") (pintype "bidirectional"))
    )
    (net (code "45") (name "Net-(U$5-VSET1)") (class "Default")
      (node (ref "R17") (pin "2") (pinfunction "2_2") (pintype "passive"))
      (node (ref "U$5") (pin "17") (pinfunction "VSET1_17") (pintype "bidirectional"))
    )
    (net (code "46") (name "Net-(U$5-VSET2)") (class "Default")
      (node (ref "R21") (pin "2") (pinfunction "2_2") (pintype "passive"))
      (node (ref "U$5") (pin "16") (pinfunction "VSET2_16") (pintype "bidirectional"))
    )
    (net (code "47") (name "Net-(U$22-LEDK1)") (class "Default")
      (node (ref "R5") (pin "2") (pinfunction "2_2") (pintype "passive"))
      (node (ref "U$22") (pin "11") (pinfunction "LEDK2_11") (pintype "bidirectional"))
      (node (ref "U$22") (pin "12") (pinfunction "LEDK1_12") (pintype "bidirectional"))
    )
    (net (code "48") (name "Net-(U$35-VCC)") (class "Default")
      (node (ref "C24") (pin "1") (pinfunction "1_1") (pintype "passive"))
      (node (ref "C25") (pin "1") (pinfunction "1_1") (pintype "passive"))
      (node (ref "C7") (pin "1") (pinfunction "1_1") (pintype "passive"))
      (node (ref "JMP4") (pin "2") (pinfunction "2_2") (pintype "passive"))
      (node (ref "U$35") (pin "8") (pinfunction "VCC_8") (pintype "bidirectional"))
    )
    (net (code "49") (name "Net-(U2-CLKOE)") (class "Default")
      (node (ref "R18") (pin "1") (pinfunction "1_1") (pintype "passive"))
      (node (ref "R20") (pin "2") (pinfunction "2_2") (pintype "passive"))
      (node (ref "U2") (pin "3") (pinfunction "CLKOE_3") (pintype "input"))
    )
    (net (code "50") (name "Net-(U4-SEL)") (class "Default")
      (node (ref "R13") (pin "2") (pinfunction "2_2") (pintype "passive"))
      (node (ref "R6") (pin "2") (pinfunction "2_2") (pintype "passive"))
      (node (ref "U4") (pin "15") (pinfunction "SEL_15") (pintype "passive"))
    )
    (net (code "51") (name "Net-(U4-~{EN})") (class "Default")
      (node (ref "JMP1") (pin "2") (pinfunction "2_2") (pintype "passive"))
      (node (ref "U4") (pin "13") (pinfunction "~{EN}_13") (pintype "passive"))
    )
    (net (code "52") (name "PPG_POWER") (class "Default")
      (node (ref "J4") (pin "1") (pinfunction "1_1") (pintype "passive"))
      (node (ref "J4") (pin "3") (pinfunction "3_3") (pintype "passive"))
      (node (ref "Q2") (pin "3") (pinfunction "D_3") (pintype "passive"))
    )
    (net (code "53") (name "QSPI-0") (class "Default")
      (node (ref "MDBT1") (pin "21") (pinfunction "P0.13/QSPI0_21") (pintype "bidirectional"))
      (node (ref "U$35") (pin "5") (pinfunction "DI(IO0)_5") (pintype "bidirectional"))
    )
    (net (code "54") (name "QSPI-1") (class "Default")
      (node (ref "MDBT1") (pin "27") (pinfunction "P0.14/QSPI1_27") (pintype "bidirectional"))
      (node (ref "U$35") (pin "2") (pinfunction "DO(IO1)_2") (pintype "bidirectional"))
    )
    (net (code "55") (name "QSPI-2") (class "Default")
      (node (ref "MDBT1") (pin "23") (pinfunction "P0.15/QSPI2_23") (pintype "bidirectional"))
      (node (ref "U$35") (pin "3") (pinfunction "WP(IO2)_3") (pintype "bidirectional"))
    )
    (net (code "56") (name "QSPI-3") (class "Default")
      (node (ref "MDBT1") (pin "28") (pinfunction "P0.16/QSPI3_28") (pintype "bidirectional"))
      (node (ref "U$35") (pin "7") (pinfunction "/HOLD(IO3)_7") (pintype "bidirectional"))
    )
    (net (code "57") (name "QSPI-CLK") (class "Default")
      (node (ref "MDBT1") (pin "26") (pinfunction "P0.17/QSPI_SCK_26") (pintype "bidirectional"))
      (node (ref "U$35") (pin "6") (pinfunction "CLK_6") (pintype "bidirectional"))
    )
    (net (code "58") (name "QSPI-CS") (class "Default")
      (node (ref "MDBT1") (pin "16") (pinfunction "P0.18/QSPI_CSN_16") (pintype "bidirectional"))
      (node (ref "U$35") (pin "1") (pinfunction "/CS_1") (pintype "bidirectional"))
    )
    (net (code "59") (name "RESET1") (class "Default")
      (node (ref "MDBT1") (pin "6") (pinfunction "RESET_6") (pintype "bidirectional"))
      (node (ref "P1") (pin "TP") (pinfunction "TP_TP") (pintype "input"))
    )
    (net (code "60") (name "RTC_INT") (class "Default")
      (node (ref "MDBT1") (pin "35") (pinfunction "P0.06/AIN2_35") (pintype "bidirectional"))
      (node (ref "R12") (pin "1") (pinfunction "1_1") (pintype "passive"))
      (node (ref "U2") (pin "4") (pinfunction "~{INT}_4") (pintype "output"))
    )
    (net (code "61") (name "S4A") (class "Default")
      (node (ref "J4") (pin "10") (pinfunction "10_10") (pintype "passive"))
      (node (ref "U4") (pin "12") (pinfunction "S4A_12") (pintype "bidirectional"))
    )
    (net (code "62") (name "S4B") (class "Default")
      (node (ref "J4") (pin "12") (pinfunction "12_12") (pintype "passive"))
      (node (ref "U4") (pin "11") (pinfunction "S4B_11") (pintype "bidirectional"))
    )
    (net (code "63") (name "SBU") (class "Default")
      (node (ref "D8") (pin "C") (pinfunction "C_C") (pintype "passive"))
      (node (ref "R2") (pin "2") (pinfunction "2_2") (pintype "passive"))
      (node (ref "R4") (pin "2") (pinfunction "2_2") (pintype "passive"))
    )
    (net (code "64") (name "SDO") (class "Default")
      (node (ref "U$22") (pin "6") (pinfunction "SDO_6") (pintype "bidirectional"))
    )
    (net (code "65") (name "SENSOR_BRD_SUPPLY") (class "Default")
      (node (ref "C20") (pin "1") (pinfunction "1_1") (pintype "passive"))
      (node (ref "C21") (pin "1") (pinfunction "1_1") (pintype "passive"))
      (node (ref "J3") (pin "1") (pinfunction "1_1") (pintype "passive"))
      (node (ref "J3") (pin "3") (pinfunction "3_3") (pintype "passive"))
      (node (ref "J3") (pin "5") (pinfunction "5_5") (pintype "passive"))
      (node (ref "J4") (pin "5") (pinfunction "5_5") (pintype "passive"))
      (node (ref "J4") (pin "7") (pinfunction "7_7") (pintype "passive"))
      (node (ref "J4") (pin "9") (pinfunction "9_9") (pintype "passive"))
      (node (ref "U$5") (pin "29") (pinfunction "LSOUT1/VOUTLDO1_29") (pintype "bidirectional"))
    )
    (net (code "66") (name "SEN_MFIO") (class "Default")
      (node (ref "J3") (pin "16") (pinfunction "16_16") (pintype "passive"))
      (node (ref "MDBT1") (pin "63") (pinfunction "P1.07_63") (pintype "bidirectional"))
    )
    (net (code "67") (name "SEN_MISO") (class "Default")
      (node (ref "J3") (pin "15") (pinfunction "15_15") (pintype "passive"))
      (node (ref "MDBT1") (pin "18") (pinfunction "P0.10/HSPI_MISO_18") (pintype "bidirectional"))
    )
    (net (code "68") (name "SEN_MOSI") (class "Default")
      (node (ref "J3") (pin "8") (pinfunction "8_8") (pintype "passive"))
      (node (ref "MDBT1") (pin "19") (pinfunction "P0.09/HSPI_MOSI_19") (pintype "bidirectional"))
    )
    (net (code "69") (name "SEN_RST") (class "Default")
      (node (ref "J3") (pin "19") (pinfunction "19_19") (pintype "passive"))
      (node (ref "MDBT1") (pin "10") (pinfunction "P1.06_10") (pintype "bidirectional"))
    )
    (net (code "70") (name "SEN_SCK") (class "Default")
      (node (ref "J3") (pin "4") (pinfunction "4_4") (pintype "passive"))
      (node (ref "MDBT1") (pin "29") (pinfunction "P0.08/HSPI_SCK_29") (pintype "bidirectional"))
    )
    (net (code "71") (name "SEN_SCL") (class "Default")
      (node (ref "J3") (pin "18") (pinfunction "18_18") (pintype "passive"))
      (node (ref "MDBT1") (pin "9") (pinfunction "P0.25/AIN4_9") (pintype "bidirectional"))
      (node (ref "R33") (pin "2") (pinfunction "2_2") (pintype "passive"))
      (node (ref "U$5") (pin "14") (pinfunction "SCL_14") (pintype "bidirectional"))
      (node (ref "U2") (pin "7") (pinfunction "SCL_7") (pintype "input"))
      (node (ref "U3") (pin "13") (pinfunction "SCL_13") (pintype "bidirectional"))
    )
    (net (code "72") (name "SEN_SDA") (class "Default")
      (node (ref "J3") (pin "17") (pinfunction "17_17") (pintype "passive"))
      (node (ref "MDBT1") (pin "8") (pinfunction "P0.24_8") (pintype "bidirectional"))
      (node (ref "R30") (pin "2") (pinfunction "2_2") (pintype "passive"))
      (node (ref "U$5") (pin "13") (pinfunction "SDA_13") (pintype "bidirectional"))
      (node (ref "U2") (pin "8") (pinfunction "SDA_8") (pintype "bidirectional"))
      (node (ref "U3") (pin "14") (pinfunction "SDA_14") (pintype "bidirectional"))
    )
    (net (code "73") (name "SHPHLD") (class "Default")
      (node (ref "JMP3") (pin "3") (pinfunction "3_3") (pintype "passive"))
      (node (ref "R25") (pin "2") (pinfunction "2_2") (pintype "passive"))
    )
    (net (code "74") (name "SW1") (class "Default")
      (node (ref "JMP2") (pin "3") (pinfunction "3_3") (pintype "passive"))
      (node (ref "MDBT1") (pin "39") (pinfunction "P0.05/AIN1_39") (pintype "bidirectional"))
    )
    (net (code "75") (name "SW3") (class "Default")
      (node (ref "JMP3") (pin "1") (pinfunction "1_1") (pintype "passive"))
      (node (ref "MDBT1") (pin "30") (pinfunction "P0.03/NFC2_30") (pintype "bidirectional"))
    )
    (net (code "76") (name "SWCLK1") (class "Default")
      (node (ref "J1") (pin "3") (pinfunction "3_3") (pintype "passive"))
      (node (ref "MDBT1") (pin "2") (pinfunction "SWDCLK_2") (pintype "bidirectional"))
      (node (ref "U4") (pin "4") (pinfunction "S2B_4") (pintype "bidirectional"))
    )
    (net (code "77") (name "SWDIO1") (class "Default")
      (node (ref "J1") (pin "4") (pinfunction "4_4") (pintype "passive"))
      (node (ref "MDBT1") (pin "4") (pinfunction "SWDIO_4") (pintype "bidirectional"))
      (node (ref "U4") (pin "1") (pinfunction "S1B_1") (pintype "bidirectional"))
    )
    (net (code "78") (name "SW_D1") (class "Default")
      (node (ref "D11") (pin "2") (pinfunction "2_2") (pintype "bidirectional"))
      (node (ref "J2") (pin "A2") (pinfunction "SSTXP1_A2") (pintype "bidirectional"))
      (node (ref "J2") (pin "B2") (pinfunction "SSTXP2_B2") (pintype "bidirectional"))
      (node (ref "U4") (pin "2") (pinfunction "D1_2") (pintype "bidirectional"))
    )
    (net (code "79") (name "SW_D2") (class "Default")
      (node (ref "D1") (pin "2") (pinfunction "2_2") (pintype "bidirectional"))
      (node (ref "J2") (pin "A3") (pinfunction "SSTXN1_A3") (pintype "bidirectional"))
      (node (ref "J2") (pin "B3") (pinfunction "SSTXN2_B3") (pintype "bidirectional"))
      (node (ref "U4") (pin "5") (pinfunction "D2_5") (pintype "bidirectional"))
    )
    (net (code "80") (name "SW_D3") (class "Default")
      (node (ref "D6") (pin "2") (pinfunction "2_2") (pintype "bidirectional"))
      (node (ref "J2") (pin "A11") (pinfunction "SSRXP2_A11") (pintype "bidirectional"))
      (node (ref "J2") (pin "B11") (pinfunction "SSRXP1_B11") (pintype "bidirectional"))
      (node (ref "U4") (pin "7") (pinfunction "D3_7") (pintype "bidirectional"))
    )
    (net (code "81") (name "SW_D4") (class "Default")
      (node (ref "D5") (pin "2") (pinfunction "2_2") (pintype "bidirectional"))
      (node (ref "J2") (pin "A10") (pinfunction "SSRXN2_A10") (pintype "bidirectional"))
      (node (ref "J2") (pin "B10") (pinfunction "SSRXN1_B10") (pintype "bidirectional"))
      (node (ref "U4") (pin "10") (pinfunction "D4_10") (pintype "bidirectional"))
    )
    (net (code "82") (name "S_INT") (class "Default")
      (node (ref "J4") (pin "8") (pinfunction "8_8") (pintype "passive"))
      (node (ref "U4") (pin "9") (pinfunction "S3A_9") (pintype "bidirectional"))
    )
    (net (code "83") (name "S_SCL") (class "Default")
      (node (ref "J4") (pin "6") (pinfunction "6_6") (pintype "passive"))
      (node (ref "U4") (pin "3") (pinfunction "S2A_3") (pintype "bidirectional"))
    )
    (net (code "84") (name "S_SDA") (class "Default")
      (node (ref "J4") (pin "4") (pinfunction "4_4") (pintype "passive"))
      (node (ref "U4") (pin "16") (pinfunction "S1A_16") (pintype "bidirectional"))
    )
    (net (code "85") (name "TFT_BL") (class "Default")
      (node (ref "MDBT1") (pin "22") (pinfunction "P1.05_22") (pintype "bidirectional"))
      (node (ref "R1") (pin "2") (pinfunction "2_2") (pintype "passive"))
    )
    (net (code "86") (name "TFT_CS") (class "Default")
      (node (ref "MDBT1") (pin "11") (pinfunction "P1.04_11") (pintype "bidirectional"))
      (node (ref "U$22") (pin "4") (pinfunction "CSX_4") (pintype "bidirectional"))
    )
    (net (code "87") (name "TFT_DC") (class "Default")
      (node (ref "MDBT1") (pin "43") (pinfunction "P1.01_43") (pintype "bidirectional"))
      (node (ref "U$22") (pin "8") (pinfunction "WRX/RS_8") (pintype "bidirectional"))
    )
    (net (code "88") (name "TFT_MOSI") (class "Default")
      (node (ref "MDBT1") (pin "51") (pinfunction "P1.13_51") (pintype "bidirectional"))
      (node (ref "U$22") (pin "7") (pinfunction "SDA_7") (pintype "bidirectional"))
    )
    (net (code "89") (name "TFT_RST") (class "Default")
      (node (ref "MDBT1") (pin "65") (pinfunction "P0.29_65") (pintype "bidirectional"))
      (node (ref "U$22") (pin "3") (pinfunction "RESET_3") (pintype "bidirectional"))
    )
    (net (code "90") (name "TFT_SCK") (class "Default")
      (node (ref "MDBT1") (pin "47") (pinfunction "P1.15_47") (pintype "bidirectional"))
      (node (ref "U$22") (pin "5") (pinfunction "DCX/SCL_5") (pintype "bidirectional"))
    )
    (net (code "91") (name "TP_INT") (class "Default")
      (node (ref "MDBT1") (pin "7") (pinfunction "P0.26/AIN5_7") (pintype "bidirectional"))
      (node (ref "U$22") (pin "16") (pinfunction "TP_INT_16") (pintype "bidirectional"))
    )
    (net (code "92") (name "TP_RST") (class "Default")
      (node (ref "MDBT1") (pin "5") (pinfunction "P0.27/AIN6_5") (pintype "bidirectional"))
      (node (ref "U$22") (pin "19") (pinfunction "TP_RST_19") (pintype "bidirectional"))
    )
    (net (code "93") (name "TP_SCL") (class "Default")
      (node (ref "MDBT1") (pin "31") (pinfunction "P1.03/TWI_31") (pintype "bidirectional"))
      (node (ref "R9") (pin "2") (pinfunction "2_2") (pintype "passive"))
      (node (ref "U$22") (pin "17") (pinfunction "TP_SCL_17") (pintype "bidirectional"))
    )
    (net (code "94") (name "TP_SDA") (class "Default")
      (node (ref "MDBT1") (pin "33") (pinfunction "P1.02/TWI_33") (pintype "bidirectional"))
      (node (ref "R11") (pin "2") (pinfunction "2_2") (pintype "passive"))
      (node (ref "U$22") (pin "18") (pinfunction "TP_SDA_18") (pintype "bidirectional"))
    )
    (net (code "95") (name "UART_TX") (class "Default")
      (node (ref "J1") (pin "2") (pinfunction "2_2") (pintype "power_in"))
      (node (ref "MDBT1") (pin "13") (pinfunction "P0.20_13") (pintype "bidirectional"))
      (node (ref "TX") (pin "TP") (pinfunction "TP_TP") (pintype "input"))
      (node (ref "U4") (pin "8") (pinfunction "S3B_8") (pintype "bidirectional"))
    )
    (net (code "96") (name "USB_D+") (class "Default")
      (node (ref "MDBT1") (pin "46") (pinfunction "D+_46") (pintype "bidirectional"))
      (node (ref "R31") (pin "2") (pinfunction "2_2") (pintype "passive"))
    )
    (net (code "97") (name "USB_D-") (class "Default")
      (node (ref "MDBT1") (pin "48") (pinfunction "D-_48") (pintype "bidirectional"))
      (node (ref "R32") (pin "2") (pinfunction "2_2") (pintype "passive"))
    )
    (net (code "98") (name "VBUS") (class "Default")
      (node (ref "MDBT1") (pin "44") (pinfunction "VBUS_44") (pintype "bidirectional"))
      (node (ref "U$5") (pin "22") (pinfunction "VBUSOUT_22") (pintype "bidirectional"))
    )
    (net (code "99") (name "VCC") (class "Default")
      (node (ref "C1") (pin "1") (pinfunction "1_1") (pintype "passive"))
      (node (ref "C3") (pin "1") (pinfunction "1_1") (pintype "passive"))
      (node (ref "C6") (pin "1") (pinfunction "1_1") (pintype "passive"))
      (node (ref "U$5") (pin "20") (pinfunction "VSYS_20") (pintype "bidirectional"))
      (node (ref "U$5") (pin "4") (pinfunction "PVDD_4") (pintype "bidirectional"))
    )
    (net (code "100") (name "VUSB2") (class "Default")
      (node (ref "C18") (pin "1") (pinfunction "1_1") (pintype "passive"))
      (node (ref "C5") (pin "1") (pinfunction "1_1") (pintype "passive"))
      (node (ref "J2") (pin "A4") (pinfunction "VBUS_A_A4") (pintype "power_in"))
      (node (ref "J2") (pin "A9") (pinfunction "VBUS_A_A9") (pintype "power_in"))
      (node (ref "J2") (pin "B4") (pinfunction "VBUS_B_B4") (pintype "power_in"))
      (node (ref "J2") (pin "B9") (pinfunction "VBUS_B_B9") (pintype "power_in"))
      (node (ref "Q2") (pin "1") (pinfunction "G_1") (pintype "passive"))
      (node (ref "R15") (pin "2") (pinfunction "2_2") (pintype "passive"))
      (node (ref "R6") (pin "1") (pinfunction "1_1") (pintype "passive"))
      (node (ref "U$5") (pin "21") (pinfunction "VBUS_21") (pintype "bidirectional"))
    )
    (net (code "101") (name "W_MFIO") (class "Default")
      (node (ref "J3") (pin "12") (pinfunction "12_12") (pintype "passive"))
      (node (ref "MDBT1") (pin "60") (pinfunction "P0.28/AIN7_60") (pintype "bidirectional"))
    )
    (net (code "102") (name "unconnected-(J3-Pad6)") (class "Default")
      (node (ref "J3") (pin "6") (pinfunction "6_6") (pintype "passive"))
    )
    (net (code "103") (name "unconnected-(J3-Pad7)") (class "Default")
      (node (ref "J3") (pin "7") (pinfunction "7_7") (pintype "passive"))
    )
    (net (code "104") (name "unconnected-(J3-Pad10)") (class "Default")
      (node (ref "J3") (pin "10") (pinfunction "10_10") (pintype "passive"))
    )
    (net (code "105") (name "unconnected-(J3-Pad13)") (class "Default")
      (node (ref "J3") (pin "13") (pinfunction "13_13") (pintype "passive"))
    )
    (net (code "106") (name "unconnected-(J4-Pad11)") (class "Default")
      (node (ref "J4") (pin "11") (pinfunction "11_11") (pintype "passive"))
    )
    (net (code "107") (name "unconnected-(J4-Pad13)") (class "Default")
      (node (ref "J4") (pin "13") (pinfunction "13_13") (pintype "passive"))
    )
    (net (code "108") (name "unconnected-(J4-Pad14)") (class "Default")
      (node (ref "J4") (pin "14") (pinfunction "14_14") (pintype "passive"))
    )
    (net (code "109") (name "unconnected-(MDBT1-P0.04{slash}AIN0-Pad37)") (class "Default")
      (node (ref "MDBT1") (pin "37") (pinfunction "P0.04/AIN0_37") (pintype "bidirectional"))
    )
    (net (code "110") (name "unconnected-(MDBT1-P0.11{slash}HSPI_CSN-Pad17)") (class "Default")
      (node (ref "MDBT1") (pin "17") (pinfunction "P0.11/HSPI_CSN_17") (pintype "bidirectional"))
    )
    (net (code "111") (name "unconnected-(MDBT1-P0.12{slash}HSPI_DCX-Pad15)") (class "Default")
      (node (ref "MDBT1") (pin "15") (pinfunction "P0.12/HSPI_DCX_15") (pintype "bidirectional"))
    )
    (net (code "112") (name "unconnected-(MDBT1-P0.22-Pad25)") (class "Default")
      (node (ref "MDBT1") (pin "25") (pinfunction "P0.22_25") (pintype "bidirectional"))
    )
    (net (code "113") (name "unconnected-(MDBT1-P0.23-Pad62)") (class "Default")
      (node (ref "MDBT1") (pin "62") (pinfunction "P0.23_62") (pintype "bidirectional"))
    )
    (net (code "114") (name "unconnected-(MDBT1-P0.30-Pad57)") (class "Default")
      (node (ref "MDBT1") (pin "57") (pinfunction "P0.30_57") (pintype "bidirectional"))
    )
    (net (code "115") (name "unconnected-(MDBT1-P0.31-Pad56)") (class "Default")
      (node (ref "MDBT1") (pin "56") (pinfunction "P0.31_56") (pintype "bidirectional"))
    )
    (net (code "116") (name "unconnected-(MDBT1-P1.00-Pad45)") (class "Default")
      (node (ref "MDBT1") (pin "45") (pinfunction "P1.00_45") (pintype "bidirectional"))
    )
    (net (code "117") (name "unconnected-(MDBT1-P1.12-Pad53)") (class "Default")
      (node (ref "MDBT1") (pin "53") (pinfunction "P1.12_53") (pintype "bidirectional"))
    )
    (net (code "118") (name "unconnected-(MDBT1-P1.14-Pad49)") (class "Default")
      (node (ref "MDBT1") (pin "49") (pinfunction "P1.14_49") (pintype "bidirectional"))
    )
    (net (code "119") (name "unconnected-(U$5-GPIO3-Pad10)") (class "Default")
      (node (ref "U$5") (pin "10") (pinfunction "GPIO3_10") (pintype "bidirectional"))
    )
    (net (code "120") (name "unconnected-(U$5-GPIO4-Pad11)") (class "Default")
      (node (ref "U$5") (pin "11") (pinfunction "GPIO4_11") (pintype "bidirectional"))
    )
    (net (code "121") (name "unconnected-(U$5-LED0-Pad25)") (class "Default")
      (node (ref "U$5") (pin "25") (pinfunction "LED0_25") (pintype "bidirectional"))
    )
    (net (code "122") (name "unconnected-(U$5-LED1-Pad26)") (class "Default")
      (node (ref "U$5") (pin "26") (pinfunction "LED1_26") (pintype "bidirectional"))
    )
    (net (code "123") (name "unconnected-(U$5-LED2-Pad27)") (class "Default")
      (node (ref "U$5") (pin "27") (pinfunction "LED2_27") (pintype "bidirectional"))
    )
    (net (code "124") (name "unconnected-(U$5-LSIN2{slash}VINLDO2-Pad30)") (class "Default")
      (node (ref "U$5") (pin "30") (pinfunction "LSIN2/VINLDO2_30") (pintype "bidirectional"))
    )
    (net (code "125") (name "unconnected-(U$5-LSOUT2{slash}VOUTLDO2-Pad31)") (class "Default")
      (node (ref "U$5") (pin "31") (pinfunction "LSOUT2/VOUTLDO2_31") (pintype "bidirectional"))
    )
    (net (code "126") (name "unconnected-(U$17-0-Pad1)") (class "Default")
      (node (ref "U$17") (pin "1") (pinfunction "0_1") (pintype "passive"))
    )
    (net (code "127") (name "unconnected-(U$17-1-Pad4)") (class "Default")
      (node (ref "U$17") (pin "4") (pinfunction "1_4") (pintype "passive"))
    )
    (net (code "128") (name "unconnected-(U$22-NC-Pad15)") (class "Default")
      (node (ref "U$22") (pin "15") (pinfunction "NC_15") (pintype "bidirectional"))
    )
    (net (code "129") (name "unconnected-(U$24-0-Pad1)") (class "Default")
      (node (ref "U$24") (pin "1") (pinfunction "0_1") (pintype "passive"))
    )
    (net (code "130") (name "unconnected-(U$24-1-Pad4)") (class "Default")
      (node (ref "U$24") (pin "4") (pinfunction "1_4") (pintype "passive"))
    )
    (net (code "131") (name "unconnected-(U2-CLKOUT-Pad6)") (class "Default")
      (node (ref "U2") (pin "6") (pinfunction "CLKOUT_6") (pintype "output"))
    )
    (net (code "132") (name "unconnected-(U2-NC-Pad1)") (class "Default")
      (node (ref "U2") (pin "1") (pinfunction "NC_1") (pintype "no_connect"))
    )
    (net (code "133") (name "unconnected-(U3-INT2-Pad9)") (class "Default")
      (node (ref "U3") (pin "9") (pinfunction "INT2_9") (pintype "bidirectional"))
    )
    (net (code "134") (name "unconnected-(U3-NC-Pad11)") (class "Default")
      (node (ref "U3") (pin "11") (pinfunction "NC_11") (pintype "bidirectional"))
    )
    (net (code "135") (name "unconnected-(U3-OCS-Pad10)") (class "Default")
      (node (ref "U3") (pin "10") (pinfunction "OCS_10") (pintype "bidirectional"))
    )
  )
)
